# RS485.net
KiCad netlist of a schematic drawn in Altium Designer
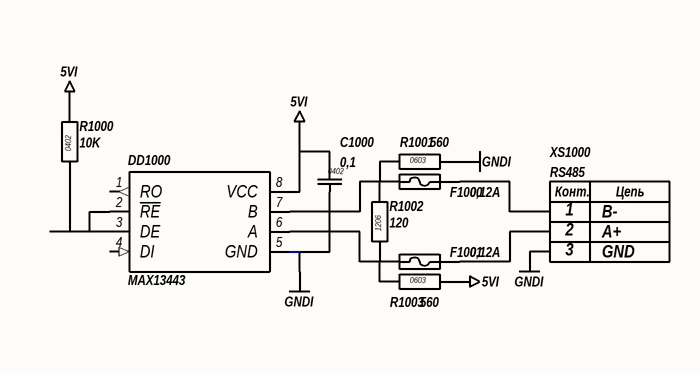
[diagram p0: RS485.SchDoc]

(export (version "E")
  (design (tool "Eeschema 10.0.6"))
  (components
    (comp (ref "C1000")
      (value "0,1")
      (footprint "CAP0402")
      (description "Конденсатор чип")
      (libsource (lib "EwgPassive") (part "CAP_0402"))
    )
    (comp (ref "DD1000")
      (value "MAX13443")
      (footprint "SO8-3.9")
      (description "Интерфейс RS485")
      (libsource (lib "EwgMicrochips") (part "MAX13443"))
    )
    (comp (ref "F1000")
      (value "0,12A")
      (footprint "MF-NSMF")
      (description "Предохранитель самовосстанавливающийся")
      (libsource (lib "EwgPassive") (part "MF-NSMF"))
    )
    (comp (ref "F1001")
      (value "0,12A")
      (footprint "MF-NSMF")
      (description "Предохранитель самовосстанавливающийся")
      (libsource (lib "EwgPassive") (part "MF-NSMF"))
    )
    (comp (ref "R1000")
      (value "10K")
      (footprint "RES0402")
      (description "Резистор чип")
      (libsource (lib "EwgPassive") (part "RES_0402"))
    )
    (comp (ref "R1001")
      (value "560")
      (footprint "RES0603")
      (description "Резистор чип")
      (libsource (lib "EwgPassive") (part "RES_0603"))
    )
    (comp (ref "R1002")
      (value "120")
      (footprint "RES1206")
      (description "Резистор чип")
      (libsource (lib "EwgPassive") (part "RES_1206"))
    )
    (comp (ref "R1003")
      (value "560")
      (footprint "RES0603")
      (description "Резистор чип")
      (libsource (lib "EwgPassive") (part "RES_0603"))
    )
    (comp (ref "XS1000")
      (value "RS485")
      (footprint "MW-3M")
      (description "Разъем")
      (libsource (lib "EwgConnectors") (part "Разъем3_1"))
    )
  )
  (nets
    (net (code "1") (name "5VI") (class "Default")
      (node (ref "C1000") (pin "1") (pintype "passive"))
      (node (ref "DD1000") (pin "8") (pinfunction "VCC_8") (pintype "passive"))
      (node (ref "R1000") (pin "2") (pintype "passive"))
      (node (ref "R1003") (pin "2") (pintype "passive"))
    )
    (net (code "2") (name "GNDI") (class "Default")
      (node (ref "C1000") (pin "2") (pintype "passive"))
      (node (ref "DD1000") (pin "5") (pinfunction "GND_5") (pintype "passive"))
      (node (ref "R1001") (pin "2") (pintype "passive"))
      (node (ref "XS1000") (pin "3") (pinfunction "GND_3") (pintype "passive"))
    )
    (net (code "3") (name "Net-(DD1000-A)") (class "Default")
      (node (ref "DD1000") (pin "6") (pinfunction "A_6") (pintype "passive"))
      (node (ref "F1001") (pin "1") (pintype "passive"))
      (node (ref "R1002") (pin "1") (pintype "passive"))
      (node (ref "R1003") (pin "1") (pintype "passive"))
    )
    (net (code "4") (name "Net-(DD1000-B)") (class "Default")
      (node (ref "DD1000") (pin "7") (pinfunction "B_7") (pintype "passive"))
      (node (ref "F1000") (pin "1") (pintype "passive"))
      (node (ref "R1001") (pin "1") (pintype "passive"))
      (node (ref "R1002") (pin "2") (pintype "passive"))
    )
    (net (code "5") (name "Net-(DD1000-DE)") (class "Default")
      (node (ref "DD1000") (pin "2") (pinfunction "~{RE}_2") (pintype "passive"))
      (node (ref "DD1000") (pin "3") (pinfunction "DE_3") (pintype "passive"))
      (node (ref "R1000") (pin "1") (pintype "passive"))
    )
    (net (code "6") (name "Net-(XS1000-A+)") (class "Default")
      (node (ref "F1001") (pin "2") (pintype "passive"))
      (node (ref "XS1000") (pin "2") (pinfunction "A+_2") (pintype "passive"))
    )
    (net (code "7") (name "Net-(XS1000-B-)") (class "Default")
      (node (ref "F1000") (pin "2") (pintype "passive"))
      (node (ref "XS1000") (pin "1") (pinfunction "B-_1") (pintype "passive"))
    )
    (net (code "8") (name "unconnected-(DD1000-DI-Pad4)") (class "Default")
      (node (ref "DD1000") (pin "4") (pinfunction "DI_4") (pintype "input"))
    )
    (net (code "9") (name "unconnected-(DD1000-RO-Pad1)") (class "Default")
      (node (ref "DD1000") (pin "1") (pinfunction "RO_1") (pintype "output"))
    )
  )
)
